# DigitHolder.net
KiCad netlist of a schematic drawn in Altium Designer
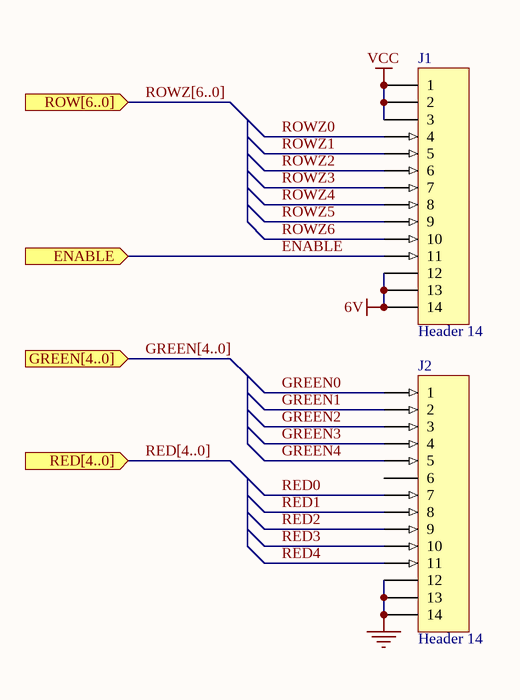
[diagram p0: DigitHolder.SCHDOC]

(export (version "E")
  (design (tool "Eeschema 10.0.6"))
  (components
    (comp (ref "J1")
      (value "Header 14")
      (footprint "HDR1X14")
      (description "Header, 14-Pin")
      (fields (field (name "MANUFACTURER") "Generic Components") (field (name "PUBLISHER") "Altium Limited"))
      (libsource (lib "Miscellaneous Connectors") (part "Header 14"))
    )
    (comp (ref "J2")
      (value "Header 14")
      (footprint "HDR1X14")
      (description "Header, 14-Pin")
      (fields (field (name "MANUFACTURER") "Generic Components") (field (name "PUBLISHER") "Altium Limited"))
      (libsource (lib "Miscellaneous Connectors") (part "Header 14"))
    )
  )
  (nets
    (net (code "1") (name "/ENABLE") (class "Default")
      (node (ref "J1") (pin "11") (pinfunction "11_11") (pintype "input"))
    )
    (net (code "2") (name "/GREEN0") (class "Default")
      (node (ref "J2") (pin "1") (pinfunction "1_1") (pintype "passive"))
    )
    (net (code "3") (name "/GREEN1") (class "Default")
      (node (ref "J2") (pin "2") (pinfunction "2_2") (pintype "passive"))
    )
    (net (code "4") (name "/GREEN2") (class "Default")
      (node (ref "J2") (pin "3") (pinfunction "3_3") (pintype "passive"))
    )
    (net (code "5") (name "/GREEN3") (class "Default")
      (node (ref "J2") (pin "4") (pinfunction "4_4") (pintype "input"))
    )
    (net (code "6") (name "/GREEN4") (class "Default")
      (node (ref "J2") (pin "5") (pinfunction "5_5") (pintype "input"))
    )
    (net (code "8") (name "/RED0") (class "Default")
      (node (ref "J2") (pin "7") (pinfunction "7_7") (pintype "input"))
    )
    (net (code "9") (name "/RED1") (class "Default")
      (node (ref "J2") (pin "8") (pinfunction "8_8") (pintype "input"))
    )
    (net (code "10") (name "/RED2") (class "Default")
      (node (ref "J2") (pin "9") (pinfunction "9_9") (pintype "input"))
    )
    (net (code "11") (name "/RED3") (class "Default")
      (node (ref "J2") (pin "10") (pinfunction "10_10") (pintype "input"))
    )
    (net (code "12") (name "/RED4") (class "Default")
      (node (ref "J2") (pin "11") (pinfunction "11_11") (pintype "input"))
    )
    (net (code "14") (name "/ROWZ0") (class "Default")
      (node (ref "J1") (pin "4") (pinfunction "4_4") (pintype "input"))
    )
    (net (code "15") (name "/ROWZ1") (class "Default")
      (node (ref "J1") (pin "5") (pinfunction "5_5") (pintype "input"))
    )
    (net (code "16") (name "/ROWZ2") (class "Default")
      (node (ref "J1") (pin "6") (pinfunction "6_6") (pintype "input"))
    )
    (net (code "17") (name "/ROWZ3") (class "Default")
      (node (ref "J1") (pin "7") (pinfunction "7_7") (pintype "input"))
    )
    (net (code "18") (name "/ROWZ4") (class "Default")
      (node (ref "J1") (pin "8") (pinfunction "8_8") (pintype "input"))
    )
    (net (code "19") (name "/ROWZ5") (class "Default")
      (node (ref "J1") (pin "9") (pinfunction "9_9") (pintype "input"))
    )
    (net (code "20") (name "/ROWZ6") (class "Default")
      (node (ref "J1") (pin "10") (pinfunction "10_10") (pintype "input"))
    )
    (net (code "22") (name "6V") (class "Default")
      (node (ref "J1") (pin "12") (pinfunction "12_12") (pintype "passive"))
      (node (ref "J1") (pin "13") (pinfunction "13_13") (pintype "passive"))
      (node (ref "J1") (pin "14") (pinfunction "14_14") (pintype "passive"))
    )
    (net (code "23") (name "GND") (class "Default")
      (node (ref "J2") (pin "12") (pinfunction "12_12") (pintype "passive"))
      (node (ref "J2") (pin "13") (pinfunction "13_13") (pintype "passive"))
      (node (ref "J2") (pin "14") (pinfunction "14_14") (pintype "passive"))
    )
    (net (code "24") (name "VCC") (class "Default")
      (node (ref "J1") (pin "1") (pinfunction "1_1") (pintype "passive"))
      (node (ref "J1") (pin "2") (pinfunction "2_2") (pintype "passive"))
      (node (ref "J1") (pin "3") (pinfunction "3_3") (pintype "passive"))
    )
    (net (code "25") (name "unconnected-(J2-Pad6)") (class "Default")
      (node (ref "J2") (pin "6") (pinfunction "6_6") (pintype "input"))
    )
  )
)
